# Kinect_Rpi_Preg.net
KiCad netlist of a schematic drawn in EAGLE
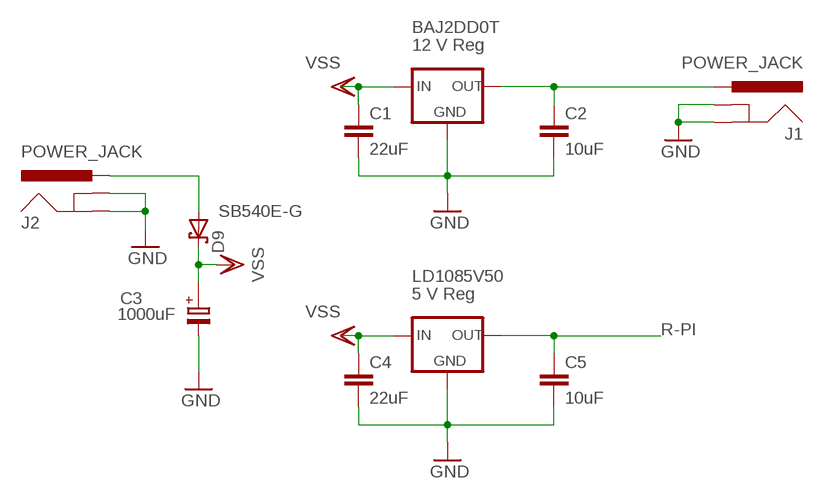
[diagram p0: schematic, sheet 1]

(export (version "E")
  (design (tool "Eeschema 10.0.6"))
  (components
    (comp (ref "BAJ2DD0T")
      (value "12 V Reg")
      (footprint "eagle-import:78MXXL")
      (libsource (lib "eagle-import") (part "78MXXL"))
    )
    (comp (ref "C1")
      (value "22uF")
      (footprint "eagle-import:C1206")
      (libsource (lib "eagle-import") (part "C-EUC1206"))
    )
    (comp (ref "C2")
      (value "10uF")
      (footprint "eagle-import:C1206")
      (libsource (lib "eagle-import") (part "C-EUC1206"))
    )
    (comp (ref "C3")
      (value "1000uF")
      (footprint "eagle-import:E5,0-10")
      (libsource (lib "eagle-import") (part "C-PR-5,0X10"))
    )
    (comp (ref "C4")
      (value "22uF")
      (footprint "eagle-import:C1206")
      (libsource (lib "eagle-import") (part "C-EUC1206"))
    )
    (comp (ref "C5")
      (value "10uF")
      (footprint "eagle-import:C1206")
      (libsource (lib "eagle-import") (part "C-EUC1206"))
    )
    (comp (ref "D9")
      (value "SB540E-G")
      (footprint "eagle-import:DO-201AD_UPRIGHT")
      (libsource (lib "eagle-import") (part "SCHOTTKY-DIODEDO-201AD_UPRIGHT"))
    )
    (comp (ref "J1")
      (value "POWER_JACK")
      (footprint "eagle-import:POWER_JACK_PTH")
      (libsource (lib "eagle-import") (part "POWER_JACK"))
    )
    (comp (ref "J2")
      (value "POWER_JACK")
      (footprint "eagle-import:POWER_JACK_PTH")
      (libsource (lib "eagle-import") (part "POWER_JACK"))
    )
    (comp (ref "LD1085V50")
      (value "5 V Reg")
      (footprint "eagle-import:78MXXL")
      (libsource (lib "eagle-import") (part "78MXXL"))
    )
  )
  (nets
    (net (code "1") (name "/R-PI") (class "Default")
      (node (ref "C5") (pin "1") (pinfunction "1_1") (pintype "passive"))
      (node (ref "LD1085V50") (pin "OUT") (pinfunction "OUT_OUT") (pintype "passive"))
    )
    (net (code "2") (name "GND") (class "Default")
      (node (ref "BAJ2DD0T") (pin "GND") (pinfunction "GND_GND") (pintype "input"))
      (node (ref "C1") (pin "2") (pinfunction "2_2") (pintype "passive"))
      (node (ref "C2") (pin "2") (pinfunction "2_2") (pintype "passive"))
      (node (ref "C3") (pin "-") (pinfunction "-_-") (pintype "passive"))
      (node (ref "C4") (pin "2") (pinfunction "2_2") (pintype "passive"))
      (node (ref "C5") (pin "2") (pinfunction "2_2") (pintype "passive"))
      (node (ref "J1") (pin "GND") (pinfunction "GND_GND") (pintype "bidirectional"))
      (node (ref "J1") (pin "GNDBREAK") (pinfunction "GNDBREAK_GNDBREAK") (pintype "bidirectional"))
      (node (ref "J2") (pin "GND") (pinfunction "GND_GND") (pintype "bidirectional"))
      (node (ref "J2") (pin "GNDBREAK") (pinfunction "GNDBREAK_GNDBREAK") (pintype "bidirectional"))
      (node (ref "LD1085V50") (pin "GND") (pinfunction "GND_GND") (pintype "input"))
    )
    (net (code "3") (name "Net-(BAJ2DD0T-PadOUT)") (class "Default")
      (node (ref "BAJ2DD0T") (pin "OUT") (pinfunction "OUT_OUT") (pintype "passive"))
      (node (ref "C2") (pin "1") (pinfunction "1_1") (pintype "passive"))
      (node (ref "J1") (pin "PWR") (pinfunction "PWR_PWR") (pintype "bidirectional"))
    )
    (net (code "4") (name "Net-(D9-A)") (class "Default")
      (node (ref "D9") (pin "1") (pinfunction "A_1") (pintype "passive"))
      (node (ref "J2") (pin "PWR") (pinfunction "PWR_PWR") (pintype "bidirectional"))
    )
    (net (code "5") (name "VSS") (class "Default")
      (node (ref "BAJ2DD0T") (pin "IN") (pinfunction "IN_IN") (pintype "input"))
      (node (ref "C1") (pin "1") (pinfunction "1_1") (pintype "passive"))
      (node (ref "C3") (pin "+") (pinfunction "+_+") (pintype "passive"))
      (node (ref "C4") (pin "1") (pinfunction "1_1") (pintype "passive"))
      (node (ref "D9") (pin "2") (pinfunction "C_2") (pintype "passive"))
      (node (ref "LD1085V50") (pin "IN") (pinfunction "IN_IN") (pintype "input"))
    )
  )
)
